# KeyboardMoudle2.net
KiCad netlist of a schematic drawn in Altium Designer
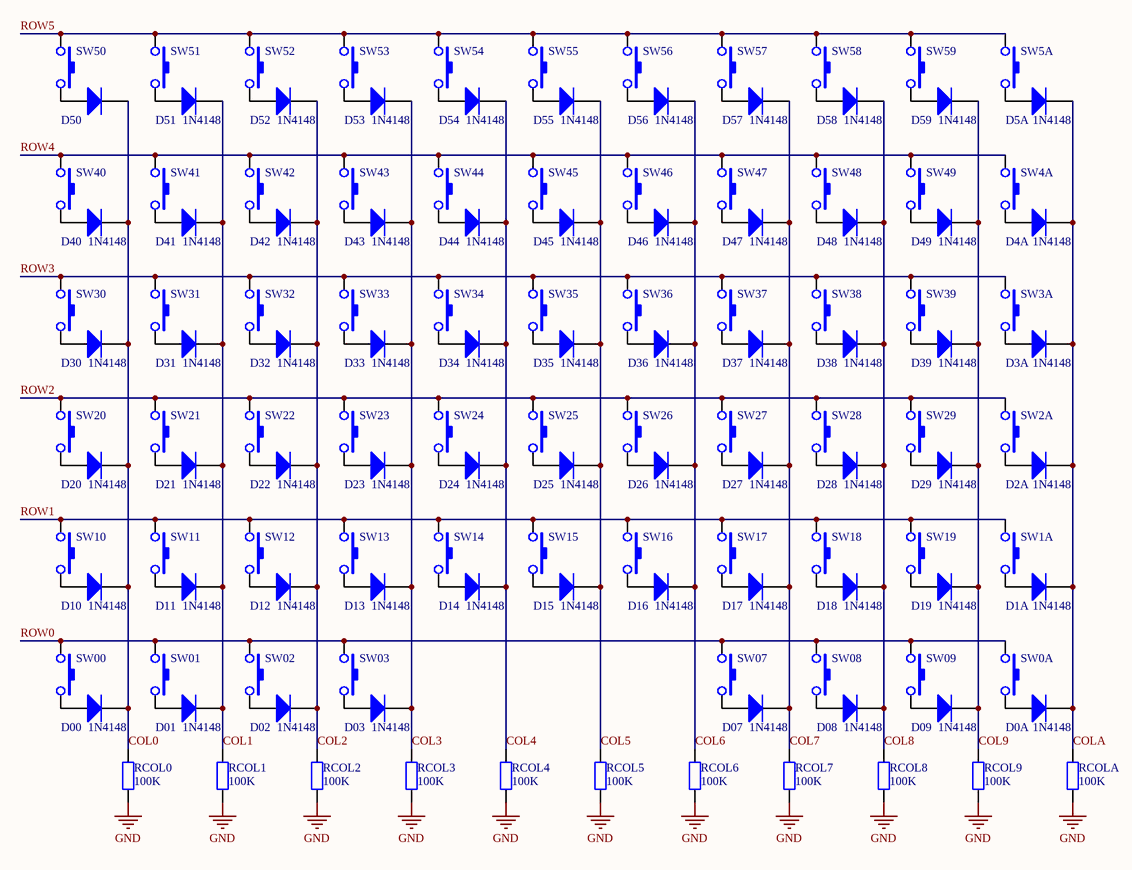
[diagram p0: KeyboardMoudle2.SchDoc]

(export (version "E")
  (design (tool "Eeschema 10.0.6"))
  (components
    (comp (ref "D00")
      (value "1N4148")
      (footprint "SOD523")
      (description "开关二极管")
      (libsource (lib "MT_Device") (part "DIO_1N4148_SOD523"))
    )
    (comp (ref "D0A")
      (value "1N4148")
      (footprint "SOD523")
      (description "开关二极管")
      (libsource (lib "MT_Device") (part "DIO_1N4148_SOD523"))
    )
    (comp (ref "D01")
      (value "1N4148")
      (footprint "SOD523")
      (description "开关二极管")
      (libsource (lib "MT_Device") (part "DIO_1N4148_SOD523"))
    )
    (comp (ref "D1A")
      (value "1N4148")
      (footprint "SOD523")
      (description "开关二极管")
      (libsource (lib "MT_Device") (part "DIO_1N4148_SOD523"))
    )
    (comp (ref "D02")
      (value "1N4148")
      (footprint "SOD523")
      (description "开关二极管")
      (libsource (lib "MT_Device") (part "DIO_1N4148_SOD523"))
    )
    (comp (ref "D2A")
      (value "1N4148")
      (footprint "SOD523")
      (description "开关二极管")
      (libsource (lib "MT_Device") (part "DIO_1N4148_SOD523"))
    )
    (comp (ref "D03")
      (value "1N4148")
      (footprint "SOD523")
      (description "开关二极管")
      (libsource (lib "MT_Device") (part "DIO_1N4148_SOD523"))
    )
    (comp (ref "D3A")
      (value "1N4148")
      (footprint "SOD523")
      (description "开关二极管")
      (libsource (lib "MT_Device") (part "DIO_1N4148_SOD523"))
    )
    (comp (ref "D4A")
      (value "1N4148")
      (footprint "SOD523")
      (description "开关二极管")
      (libsource (lib "MT_Device") (part "DIO_1N4148_SOD523"))
    )
    (comp (ref "D5A")
      (value "1N4148")
      (footprint "SOD523")
      (description "开关二极管")
      (libsource (lib "MT_Device") (part "DIO_1N4148_SOD523"))
    )
    (comp (ref "D07")
      (value "1N4148")
      (footprint "SOD523")
      (description "开关二极管")
      (libsource (lib "MT_Device") (part "DIO_1N4148_SOD523"))
    )
    (comp (ref "D08")
      (value "1N4148")
      (footprint "SOD523")
      (description "开关二极管")
      (libsource (lib "MT_Device") (part "DIO_1N4148_SOD523"))
    )
    (comp (ref "D09")
      (value "1N4148")
      (footprint "SOD523")
      (description "开关二极管")
      (libsource (lib "MT_Device") (part "DIO_1N4148_SOD523"))
    )
    (comp (ref "D10")
      (value "1N4148")
      (footprint "SOD523")
      (description "开关二极管")
      (libsource (lib "MT_Device") (part "DIO_1N4148_SOD523"))
    )
    (comp (ref "D11")
      (value "1N4148")
      (footprint "SOD523")
      (description "开关二极管")
      (libsource (lib "MT_Device") (part "DIO_1N4148_SOD523"))
    )
    (comp (ref "D12")
      (value "1N4148")
      (footprint "SOD523")
      (description "开关二极管")
      (libsource (lib "MT_Device") (part "DIO_1N4148_SOD523"))
    )
    (comp (ref "D13")
      (value "1N4148")
      (footprint "SOD523")
      (description "开关二极管")
      (libsource (lib "MT_Device") (part "DIO_1N4148_SOD523"))
    )
    (comp (ref "D14")
      (value "1N4148")
      (footprint "SOD523")
      (description "开关二极管")
      (libsource (lib "MT_Device") (part "DIO_1N4148_SOD523"))
    )
    (comp (ref "D15")
      (value "1N4148")
      (footprint "SOD523")
      (description "开关二极管")
      (libsource (lib "MT_Device") (part "DIO_1N4148_SOD523"))
    )
    (comp (ref "D16")
      (value "1N4148")
      (footprint "SOD523")
      (description "开关二极管")
      (libsource (lib "MT_Device") (part "DIO_1N4148_SOD523"))
    )
    (comp (ref "D17")
      (value "1N4148")
      (footprint "SOD523")
      (description "开关二极管")
      (libsource (lib "MT_Device") (part "DIO_1N4148_SOD523"))
    )
    (comp (ref "D18")
      (value "1N4148")
      (footprint "SOD523")
      (description "开关二极管")
      (libsource (lib "MT_Device") (part "DIO_1N4148_SOD523"))
    )
    (comp (ref "D19")
      (value "1N4148")
      (footprint "SOD523")
      (description "开关二极管")
      (libsource (lib "MT_Device") (part "DIO_1N4148_SOD523"))
    )
    (comp (ref "D20")
      (value "1N4148")
      (footprint "SOD523")
      (description "开关二极管")
      (libsource (lib "MT_Device") (part "DIO_1N4148_SOD523"))
    )
    (comp (ref "D21")
      (value "1N4148")
      (footprint "SOD523")
      (description "开关二极管")
      (libsource (lib "MT_Device") (part "DIO_1N4148_SOD523"))
    )
    (comp (ref "D22")
      (value "1N4148")
      (footprint "SOD523")
      (description "开关二极管")
      (libsource (lib "MT_Device") (part "DIO_1N4148_SOD523"))
    )
    (comp (ref "D23")
      (value "1N4148")
      (footprint "SOD523")
      (description "开关二极管")
      (libsource (lib "MT_Device") (part "DIO_1N4148_SOD523"))
    )
    (comp (ref "D24")
      (value "1N4148")
      (footprint "SOD523")
      (description "开关二极管")
      (libsource (lib "MT_Device") (part "DIO_1N4148_SOD523"))
    )
    (comp (ref "D25")
      (value "1N4148")
      (footprint "SOD523")
      (description "开关二极管")
      (libsource (lib "MT_Device") (part "DIO_1N4148_SOD523"))
    )
    (comp (ref "D26")
      (value "1N4148")
      (footprint "SOD523")
      (description "开关二极管")
      (libsource (lib "MT_Device") (part "DIO_1N4148_SOD523"))
    )
    (comp (ref "D27")
      (value "1N4148")
      (footprint "SOD523")
      (description "开关二极管")
      (libsource (lib "MT_Device") (part "DIO_1N4148_SOD523"))
    )
    (comp (ref "D28")
      (value "1N4148")
      (footprint "SOD523")
      (description "开关二极管")
      (libsource (lib "MT_Device") (part "DIO_1N4148_SOD523"))
    )
    (comp (ref "D29")
      (value "1N4148")
      (footprint "SOD523")
      (description "开关二极管")
      (libsource (lib "MT_Device") (part "DIO_1N4148_SOD523"))
    )
    (comp (ref "D30")
      (value "1N4148")
      (footprint "SOD523")
      (description "开关二极管")
      (libsource (lib "MT_Device") (part "DIO_1N4148_SOD523"))
    )
    (comp (ref "D31")
      (value "1N4148")
      (footprint "SOD523")
      (description "开关二极管")
      (libsource (lib "MT_Device") (part "DIO_1N4148_SOD523"))
    )
    (comp (ref "D32")
      (value "1N4148")
      (footprint "SOD523")
      (description "开关二极管")
      (libsource (lib "MT_Device") (part "DIO_1N4148_SOD523"))
    )
    (comp (ref "D33")
      (value "1N4148")
      (footprint "SOD523")
      (description "开关二极管")
      (libsource (lib "MT_Device") (part "DIO_1N4148_SOD523"))
    )
    (comp (ref "D34")
      (value "1N4148")
      (footprint "SOD523")
      (description "开关二极管")
      (libsource (lib "MT_Device") (part "DIO_1N4148_SOD523"))
    )
    (comp (ref "D35")
      (value "1N4148")
      (footprint "SOD523")
      (description "开关二极管")
      (libsource (lib "MT_Device") (part "DIO_1N4148_SOD523"))
    )
    (comp (ref "D36")
      (value "1N4148")
      (footprint "SOD523")
      (description "开关二极管")
      (libsource (lib "MT_Device") (part "DIO_1N4148_SOD523"))
    )
    (comp (ref "D37")
      (value "1N4148")
      (footprint "SOD523")
      (description "开关二极管")
      (libsource (lib "MT_Device") (part "DIO_1N4148_SOD523"))
    )
    (comp (ref "D38")
      (value "1N4148")
      (footprint "SOD523")
      (description "开关二极管")
      (libsource (lib "MT_Device") (part "DIO_1N4148_SOD523"))
    )
    (comp (ref "D39")
      (value "1N4148")
      (footprint "SOD523")
      (description "开关二极管")
      (libsource (lib "MT_Device") (part "DIO_1N4148_SOD523"))
    )
    (comp (ref "D40")
      (value "1N4148")
      (footprint "SOD523")
      (description "开关二极管")
      (libsource (lib "MT_Device") (part "DIO_1N4148_SOD523"))
    )
    (comp (ref "D41")
      (value "1N4148")
      (footprint "SOD523")
      (description "开关二极管")
      (libsource (lib "MT_Device") (part "DIO_1N4148_SOD523"))
    )
    (comp (ref "D42")
      (value "1N4148")
      (footprint "SOD523")
      (description "开关二极管")
      (libsource (lib "MT_Device") (part "DIO_1N4148_SOD523"))
    )
    (comp (ref "D43")
      (value "1N4148")
      (footprint "SOD523")
      (description "开关二极管")
      (libsource (lib "MT_Device") (part "DIO_1N4148_SOD523"))
    )
    (comp (ref "D44")
      (value "1N4148")
      (footprint "SOD523")
      (description "开关二极管")
      (libsource (lib "MT_Device") (part "DIO_1N4148_SOD523"))
    )
    (comp (ref "D45")
      (value "1N4148")
      (footprint "SOD523")
      (description "开关二极管")
      (libsource (lib "MT_Device") (part "DIO_1N4148_SOD523"))
    )
    (comp (ref "D46")
      (value "1N4148")
      (footprint "SOD523")
      (description "开关二极管")
      (libsource (lib "MT_Device") (part "DIO_1N4148_SOD523"))
    )
    (comp (ref "D47")
      (value "1N4148")
      (footprint "SOD523")
      (description "开关二极管")
      (libsource (lib "MT_Device") (part "DIO_1N4148_SOD523"))
    )
    (comp (ref "D48")
      (value "1N4148")
      (footprint "SOD523")
      (description "开关二极管")
      (libsource (lib "MT_Device") (part "DIO_1N4148_SOD523"))
    )
    (comp (ref "D49")
      (value "1N4148")
      (footprint "SOD523")
      (description "开关二极管")
      (libsource (lib "MT_Device") (part "DIO_1N4148_SOD523"))
    )
    (comp (ref "D50")
      (value "~")
      (footprint "SOD523")
      (description "开关二极管")
      (libsource (lib "MT_Device") (part "DIO_1N4148_SOD523"))
    )
    (comp (ref "D51")
      (value "1N4148")
      (footprint "SOD523")
      (description "开关二极管")
      (libsource (lib "MT_Device") (part "DIO_1N4148_SOD523"))
    )
    (comp (ref "D52")
      (value "1N4148")
      (footprint "SOD523")
      (description "开关二极管")
      (libsource (lib "MT_Device") (part "DIO_1N4148_SOD523"))
    )
    (comp (ref "D53")
      (value "1N4148")
      (footprint "SOD523")
      (description "开关二极管")
      (libsource (lib "MT_Device") (part "DIO_1N4148_SOD523"))
    )
    (comp (ref "D54")
      (value "1N4148")
      (footprint "SOD523")
      (description "开关二极管")
      (libsource (lib "MT_Device") (part "DIO_1N4148_SOD523"))
    )
    (comp (ref "D55")
      (value "1N4148")
      (footprint "SOD523")
      (description "开关二极管")
      (libsource (lib "MT_Device") (part "DIO_1N4148_SOD523"))
    )
    (comp (ref "D56")
      (value "1N4148")
      (footprint "SOD523")
      (description "开关二极管")
      (libsource (lib "MT_Device") (part "DIO_1N4148_SOD523"))
    )
    (comp (ref "D57")
      (value "1N4148")
      (footprint "SOD523")
      (description "开关二极管")
      (libsource (lib "MT_Device") (part "DIO_1N4148_SOD523"))
    )
    (comp (ref "D58")
      (value "1N4148")
      (footprint "SOD523")
      (description "开关二极管")
      (libsource (lib "MT_Device") (part "DIO_1N4148_SOD523"))
    )
    (comp (ref "D59")
      (value "1N4148")
      (footprint "SOD523")
      (description "开关二极管")
      (libsource (lib "MT_Device") (part "DIO_1N4148_SOD523"))
    )
    (comp (ref "RCOL0")
      (value "100K")
      (footprint "R_0603")
      (description "电阻 0603")
      (libsource (lib "MT_Device") (part "RES_0603"))
    )
    (comp (ref "RCOL1")
      (value "100K")
      (footprint "R_0603")
      (description "电阻 0603")
      (libsource (lib "MT_Device") (part "RES_0603"))
    )
    (comp (ref "RCOL2")
      (value "100K")
      (footprint "R_0603")
      (description "电阻 0603")
      (libsource (lib "MT_Device") (part "RES_0603"))
    )
    (comp (ref "RCOL3")
      (value "100K")
      (footprint "R_0603")
      (description "电阻 0603")
      (libsource (lib "MT_Device") (part "RES_0603"))
    )
    (comp (ref "RCOL4")
      (value "100K")
      (footprint "R_0603")
      (description "电阻 0603")
      (libsource (lib "MT_Device") (part "RES_0603"))
    )
    (comp (ref "RCOL5")
      (value "100K")
      (footprint "R_0603")
      (description "电阻 0603")
      (libsource (lib "MT_Device") (part "RES_0603"))
    )
    (comp (ref "RCOL6")
      (value "100K")
      (footprint "R_0603")
      (description "电阻 0603")
      (libsource (lib "MT_Device") (part "RES_0603"))
    )
    (comp (ref "RCOL7")
      (value "100K")
      (footprint "R_0603")
      (description "电阻 0603")
      (libsource (lib "MT_Device") (part "RES_0603"))
    )
    (comp (ref "RCOL8")
      (value "100K")
      (footprint "R_0603")
      (description "电阻 0603")
      (libsource (lib "MT_Device") (part "RES_0603"))
    )
    (comp (ref "RCOL9")
      (value "100K")
      (footprint "R_0603")
      (description "电阻 0603")
      (libsource (lib "MT_Device") (part "RES_0603"))
    )
    (comp (ref "RCOLA")
      (value "100K")
      (footprint "R_0603")
      (description "电阻 0603")
      (libsource (lib "MT_Device") (part "RES_0603"))
    )
    (comp (ref "SW00")
      (value "SWITCH_KAILH_1350")
      (footprint "SWITCH_KAILH_1350")
      (description "凯华机械矮轴1350")
      (libsource (lib "MT_Device") (part "SWITCH_KAILH_1350"))
    )
    (comp (ref "SW0A")
      (value "SWITCH_KAILH_1350")
      (footprint "SWITCH_KAILH_1350")
      (description "凯华机械矮轴1350")
      (libsource (lib "MT_Device") (part "SWITCH_KAILH_1350"))
    )
    (comp (ref "SW01")
      (value "SWITCH_KAILH_1350")
      (footprint "SWITCH_KAILH_1350")
      (description "凯华机械矮轴1350")
      (libsource (lib "MT_Device") (part "SWITCH_KAILH_1350"))
    )
    (comp (ref "SW1A")
      (value "SWITCH_KAILH_1350")
      (footprint "SWITCH_KAILH_1350")
      (description "凯华机械矮轴1350")
      (libsource (lib "MT_Device") (part "SWITCH_KAILH_1350"))
    )
    (comp (ref "SW02")
      (value "SWITCH_KAILH_1350")
      (footprint "SWITCH_KAILH_1350")
      (description "凯华机械矮轴1350")
      (libsource (lib "MT_Device") (part "SWITCH_KAILH_1350"))
    )
    (comp (ref "SW2A")
      (value "SWITCH_KAILH_1350")
      (footprint "SWITCH_KAILH_1350")
      (description "凯华机械矮轴1350")
      (libsource (lib "MT_Device") (part "SWITCH_KAILH_1350"))
    )
    (comp (ref "SW03")
      (value "SWITCH_KAILH_1350")
      (footprint "SWITCH_KAILH_1350")
      (description "凯华机械矮轴1350")
      (libsource (lib "MT_Device") (part "SWITCH_KAILH_1350"))
    )
    (comp (ref "SW3A")
      (value "SWITCH_KAILH_1350")
      (footprint "SWITCH_KAILH_1350")
      (description "凯华机械矮轴1350")
      (libsource (lib "MT_Device") (part "SWITCH_KAILH_1350"))
    )
    (comp (ref "SW4A")
      (value "SWITCH_KAILH_1350")
      (footprint "SWITCH_KAILH_1350")
      (description "凯华机械矮轴1350")
      (libsource (lib "MT_Device") (part "SWITCH_KAILH_1350"))
    )
    (comp (ref "SW5A")
      (value "SWITCH_KAILH_1350")
      (footprint "SWITCH_KAILH_1350")
      (description "凯华机械矮轴1350")
      (libsource (lib "MT_Device") (part "SWITCH_KAILH_1350"))
    )
    (comp (ref "SW07")
      (value "SWITCH_KAILH_1350")
      (footprint "SWITCH_KAILH_1350")
      (description "凯华机械矮轴1350")
      (libsource (lib "MT_Device") (part "SWITCH_KAILH_1350"))
    )
    (comp (ref "SW08")
      (value "SWITCH_KAILH_1350")
      (footprint "SWITCH_KAILH_1350")
      (description "凯华机械矮轴1350")
      (libsource (lib "MT_Device") (part "SWITCH_KAILH_1350"))
    )
    (comp (ref "SW09")
      (value "SWITCH_KAILH_1350")
      (footprint "SWITCH_KAILH_1350")
      (description "凯华机械矮轴1350")
      (libsource (lib "MT_Device") (part "SWITCH_KAILH_1350"))
    )
    (comp (ref "SW10")
      (value "SWITCH_KAILH_1350")
      (footprint "SWITCH_KAILH_1350")
      (description "凯华机械矮轴1350")
      (libsource (lib "MT_Device") (part "SWITCH_KAILH_1350"))
    )
    (comp (ref "SW11")
      (value "SWITCH_KAILH_1350")
      (footprint "SWITCH_KAILH_1350")
      (description "凯华机械矮轴1350")
      (libsource (lib "MT_Device") (part "SWITCH_KAILH_1350"))
    )
    (comp (ref "SW12")
      (value "SWITCH_KAILH_1350")
      (footprint "SWITCH_KAILH_1350")
      (description "凯华机械矮轴1350")
      (libsource (lib "MT_Device") (part "SWITCH_KAILH_1350"))
    )
    (comp (ref "SW13")
      (value "SWITCH_KAILH_1350")
      (footprint "SWITCH_KAILH_1350")
      (description "凯华机械矮轴1350")
      (libsource (lib "MT_Device") (part "SWITCH_KAILH_1350"))
    )
    (comp (ref "SW14")
      (value "SWITCH_KAILH_1350")
      (footprint "SWITCH_KAILH_1350")
      (description "凯华机械矮轴1350")
      (libsource (lib "MT_Device") (part "SWITCH_KAILH_1350"))
    )
    (comp (ref "SW15")
      (value "SWITCH_KAILH_1350")
      (footprint "SWITCH_KAILH_1350")
      (description "凯华机械矮轴1350")
      (libsource (lib "MT_Device") (part "SWITCH_KAILH_1350"))
    )
    (comp (ref "SW16")
      (value "SWITCH_KAILH_1350")
      (footprint "SWITCH_KAILH_1350")
      (description "凯华机械矮轴1350")
      (libsource (lib "MT_Device") (part "SWITCH_KAILH_1350"))
    )
    (comp (ref "SW17")
      (value "SWITCH_KAILH_1350")
      (footprint "SWITCH_KAILH_1350")
      (description "凯华机械矮轴1350")
      (libsource (lib "MT_Device") (part "SWITCH_KAILH_1350"))
    )
    (comp (ref "SW18")
      (value "SWITCH_KAILH_1350")
      (footprint "SWITCH_KAILH_1350")
      (description "凯华机械矮轴1350")
      (libsource (lib "MT_Device") (part "SWITCH_KAILH_1350"))
    )
    (comp (ref "SW19")
      (value "SWITCH_KAILH_1350")
      (footprint "SWITCH_KAILH_1350")
      (description "凯华机械矮轴1350")
      (libsource (lib "MT_Device") (part "SWITCH_KAILH_1350"))
    )
    (comp (ref "SW20")
      (value "SWITCH_KAILH_1350")
      (footprint "SWITCH_KAILH_1350")
      (description "凯华机械矮轴1350")
      (libsource (lib "MT_Device") (part "SWITCH_KAILH_1350"))
    )
    (comp (ref "SW21")
      (value "SWITCH_KAILH_1350")
      (footprint "SWITCH_KAILH_1350")
      (description "凯华机械矮轴1350")
      (libsource (lib "MT_Device") (part "SWITCH_KAILH_1350"))
    )
    (comp (ref "SW22")
      (value "SWITCH_KAILH_1350")
      (footprint "SWITCH_KAILH_1350")
      (description "凯华机械矮轴1350")
      (libsource (lib "MT_Device") (part "SWITCH_KAILH_1350"))
    )
    (comp (ref "SW23")
      (value "SWITCH_KAILH_1350")
      (footprint "SWITCH_KAILH_1350")
      (description "凯华机械矮轴1350")
      (libsource (lib "MT_Device") (part "SWITCH_KAILH_1350"))
    )
    (comp (ref "SW24")
      (value "SWITCH_KAILH_1350")
      (footprint "SWITCH_KAILH_1350")
      (description "凯华机械矮轴1350")
      (libsource (lib "MT_Device") (part "SWITCH_KAILH_1350"))
    )
    (comp (ref "SW25")
      (value "SWITCH_KAILH_1350")
      (footprint "SWITCH_KAILH_1350")
      (description "凯华机械矮轴1350")
      (libsource (lib "MT_Device") (part "SWITCH_KAILH_1350"))
    )
    (comp (ref "SW26")
      (value "SWITCH_KAILH_1350")
      (footprint "SWITCH_KAILH_1350")
      (description "凯华机械矮轴1350")
      (libsource (lib "MT_Device") (part "SWITCH_KAILH_1350"))
    )
    (comp (ref "SW27")
      (value "SWITCH_KAILH_1350")
      (footprint "SWITCH_KAILH_1350")
      (description "凯华机械矮轴1350")
      (libsource (lib "MT_Device") (part "SWITCH_KAILH_1350"))
    )
    (comp (ref "SW28")
      (value "SWITCH_KAILH_1350")
      (footprint "SWITCH_KAILH_1350")
      (description "凯华机械矮轴1350")
      (libsource (lib "MT_Device") (part "SWITCH_KAILH_1350"))
    )
    (comp (ref "SW29")
      (value "SWITCH_KAILH_1350")
      (footprint "SWITCH_KAILH_1350")
      (description "凯华机械矮轴1350")
      (libsource (lib "MT_Device") (part "SWITCH_KAILH_1350"))
    )
    (comp (ref "SW30")
      (value "SWITCH_KAILH_1350")
      (footprint "SWITCH_KAILH_1350")
      (description "凯华机械矮轴1350")
      (libsource (lib "MT_Device") (part "SWITCH_KAILH_1350"))
    )
    (comp (ref "SW31")
      (value "SWITCH_KAILH_1350")
      (footprint "SWITCH_KAILH_1350")
      (description "凯华机械矮轴1350")
      (libsource (lib "MT_Device") (part "SWITCH_KAILH_1350"))
    )
    (comp (ref "SW32")
      (value "SWITCH_KAILH_1350")
      (footprint "SWITCH_KAILH_1350")
      (description "凯华机械矮轴1350")
      (libsource (lib "MT_Device") (part "SWITCH_KAILH_1350"))
    )
    (comp (ref "SW33")
      (value "SWITCH_KAILH_1350")
      (footprint "SWITCH_KAILH_1350")
      (description "凯华机械矮轴1350")
      (libsource (lib "MT_Device") (part "SWITCH_KAILH_1350"))
    )
    (comp (ref "SW34")
      (value "SWITCH_KAILH_1350")
      (footprint "SWITCH_KAILH_1350")
      (description "凯华机械矮轴1350")
      (libsource (lib "MT_Device") (part "SWITCH_KAILH_1350"))
    )
    (comp (ref "SW35")
      (value "SWITCH_KAILH_1350")
      (footprint "SWITCH_KAILH_1350")
      (description "凯华机械矮轴1350")
      (libsource (lib "MT_Device") (part "SWITCH_KAILH_1350"))
    )
    (comp (ref "SW36")
      (value "SWITCH_KAILH_1350")
      (footprint "SWITCH_KAILH_1350")
      (description "凯华机械矮轴1350")
      (libsource (lib "MT_Device") (part "SWITCH_KAILH_1350"))
    )
    (comp (ref "SW37")
      (value "SWITCH_KAILH_1350")
      (footprint "SWITCH_KAILH_1350")
      (description "凯华机械矮轴1350")
      (libsource (lib "MT_Device") (part "SWITCH_KAILH_1350"))
    )
    (comp (ref "SW38")
      (value "SWITCH_KAILH_1350")
      (footprint "SWITCH_KAILH_1350")
      (description "凯华机械矮轴1350")
      (libsource (lib "MT_Device") (part "SWITCH_KAILH_1350"))
    )
    (comp (ref "SW39")
      (value "SWITCH_KAILH_1350")
      (footprint "SWITCH_KAILH_1350")
      (description "凯华机械矮轴1350")
      (libsource (lib "MT_Device") (part "SWITCH_KAILH_1350"))
    )
    (comp (ref "SW40")
      (value "SWITCH_KAILH_1350")
      (footprint "SWITCH_KAILH_1350")
      (description "凯华机械矮轴1350")
      (libsource (lib "MT_Device") (part "SWITCH_KAILH_1350"))
    )
    (comp (ref "SW41")
      (value "SWITCH_KAILH_1350")
      (footprint "SWITCH_KAILH_1350")
      (description "凯华机械矮轴1350")
      (libsource (lib "MT_Device") (part "SWITCH_KAILH_1350"))
    )
    (comp (ref "SW42")
      (value "SWITCH_KAILH_1350")
      (footprint "SWITCH_KAILH_1350")
      (description "凯华机械矮轴1350")
      (libsource (lib "MT_Device") (part "SWITCH_KAILH_1350"))
    )
    (comp (ref "SW43")
      (value "SWITCH_KAILH_1350")
      (footprint "SWITCH_KAILH_1350")
      (description "凯华机械矮轴1350")
      (libsource (lib "MT_Device") (part "SWITCH_KAILH_1350"))
    )
    (comp (ref "SW44")
      (value "SWITCH_KAILH_1350")
      (footprint "SWITCH_KAILH_1350")
      (description "凯华机械矮轴1350")
      (libsource (lib "MT_Device") (part "SWITCH_KAILH_1350"))
    )
    (comp (ref "SW45")
      (value "SWITCH_KAILH_1350")
      (footprint "SWITCH_KAILH_1350")
      (description "凯华机械矮轴1350")
      (libsource (lib "MT_Device") (part "SWITCH_KAILH_1350"))
    )
    (comp (ref "SW46")
      (value "SWITCH_KAILH_1350")
      (footprint "SWITCH_KAILH_1350")
      (description "凯华机械矮轴1350")
      (libsource (lib "MT_Device") (part "SWITCH_KAILH_1350"))
    )
    (comp (ref "SW47")
      (value "SWITCH_KAILH_1350")
      (footprint "SWITCH_KAILH_1350")
      (description "凯华机械矮轴1350")
      (libsource (lib "MT_Device") (part "SWITCH_KAILH_1350"))
    )
    (comp (ref "SW48")
      (value "SWITCH_KAILH_1350")
      (footprint "SWITCH_KAILH_1350")
      (description "凯华机械矮轴1350")
      (libsource (lib "MT_Device") (part "SWITCH_KAILH_1350"))
    )
    (comp (ref "SW49")
      (value "SWITCH_KAILH_1350")
      (footprint "SWITCH_KAILH_1350")
      (description "凯华机械矮轴1350")
      (libsource (lib "MT_Device") (part "SWITCH_KAILH_1350"))
    )
    (comp (ref "SW50")
      (value "SWITCH_KAILH_1350")
      (footprint "SWITCH_KAILH_1350")
      (description "凯华机械矮轴1350")
      (libsource (lib "MT_Device") (part "SWITCH_KAILH_1350"))
    )
    (comp (ref "SW51")
      (value "SWITCH_KAILH_1350")
      (footprint "SWITCH_KAILH_1350")
      (description "凯华机械矮轴1350")
      (libsource (lib "MT_Device") (part "SWITCH_KAILH_1350"))
    )
    (comp (ref "SW52")
      (value "SWITCH_KAILH_1350")
      (footprint "SWITCH_KAILH_1350")
      (description "凯华机械矮轴1350")
      (libsource (lib "MT_Device") (part "SWITCH_KAILH_1350"))
    )
    (comp (ref "SW53")
      (value "SWITCH_KAILH_1350")
      (footprint "SWITCH_KAILH_1350")
      (description "凯华机械矮轴1350")
      (libsource (lib "MT_Device") (part "SWITCH_KAILH_1350"))
    )
    (comp (ref "SW54")
      (value "SWITCH_KAILH_1350")
      (footprint "SWITCH_KAILH_1350")
      (description "凯华机械矮轴1350")
      (libsource (lib "MT_Device") (part "SWITCH_KAILH_1350"))
    )
    (comp (ref "SW55")
      (value "SWITCH_KAILH_1350")
      (footprint "SWITCH_KAILH_1350")
      (description "凯华机械矮轴1350")
      (libsource (lib "MT_Device") (part "SWITCH_KAILH_1350"))
    )
    (comp (ref "SW56")
      (value "SWITCH_KAILH_1350")
      (footprint "SWITCH_KAILH_1350")
      (description "凯华机械矮轴1350")
      (libsource (lib "MT_Device") (part "SWITCH_KAILH_1350"))
    )
    (comp (ref "SW57")
      (value "SWITCH_KAILH_1350")
      (footprint "SWITCH_KAILH_1350")
      (description "凯华机械矮轴1350")
      (libsource (lib "MT_Device") (part "SWITCH_KAILH_1350"))
    )
    (comp (ref "SW58")
      (value "SWITCH_KAILH_1350")
      (footprint "SWITCH_KAILH_1350")
      (description "凯华机械矮轴1350")
      (libsource (lib "MT_Device") (part "SWITCH_KAILH_1350"))
    )
    (comp (ref "SW59")
      (value "SWITCH_KAILH_1350")
      (footprint "SWITCH_KAILH_1350")
      (description "凯华机械矮轴1350")
      (libsource (lib "MT_Device") (part "SWITCH_KAILH_1350"))
    )
  )
  (nets
    (net (code "1") (name "/COL0") (class "Default")
      (node (ref "D00") (pin "2") (pinfunction "K_2") (pintype "passive"))
      (node (ref "D10") (pin "2") (pinfunction "K_2") (pintype "passive"))
      (node (ref "D20") (pin "2") (pinfunction "K_2") (pintype "passive"))
      (node (ref "D30") (pin "2") (pinfunction "K_2") (pintype "passive"))
      (node (ref "D40") (pin "2") (pinfunction "K_2") (pintype "passive"))
      (node (ref "D50") (pin "2") (pinfunction "K_2") (pintype "passive"))
      (node (ref "RCOL0") (pin "2") (pinfunction "2_2") (pintype "passive"))
    )
    (net (code "2") (name "/COL1") (class "Default")
      (node (ref "D01") (pin "2") (pinfunction "K_2") (pintype "passive"))
      (node (ref "D11") (pin "2") (pinfunction "K_2") (pintype "passive"))
      (node (ref "D21") (pin "2") (pinfunction "K_2") (pintype "passive"))
      (node (ref "D31") (pin "2") (pinfunction "K_2") (pintype "passive"))
      (node (ref "D41") (pin "2") (pinfunction "K_2") (pintype "passive"))
      (node (ref "D51") (pin "2") (pinfunction "K_2") (pintype "passive"))
      (node (ref "RCOL1") (pin "2") (pinfunction "2_2") (pintype "passive"))
    )
    (net (code "3") (name "/COL2") (class "Default")
      (node (ref "D02") (pin "2") (pinfunction "K_2") (pintype "passive"))
      (node (ref "D12") (pin "2") (pinfunction "K_2") (pintype "passive"))
      (node (ref "D22") (pin "2") (pinfunction "K_2") (pintype "passive"))
      (node (ref "D32") (pin "2") (pinfunction "K_2") (pintype "passive"))
      (node (ref "D42") (pin "2") (pinfunction "K_2") (pintype "passive"))
      (node (ref "D52") (pin "2") (pinfunction "K_2") (pintype "passive"))
      (node (ref "RCOL2") (pin "2") (pinfunction "2_2") (pintype "passive"))
    )
    (net (code "4") (name "/COL3") (class "Default")
      (node (ref "D03") (pin "2") (pinfunction "K_2") (pintype "passive"))
      (node (ref "D13") (pin "2") (pinfunction "K_2") (pintype "passive"))
      (node (ref "D23") (pin "2") (pinfunction "K_2") (pintype "passive"))
      (node (ref "D33") (pin "2") (pinfunction "K_2") (pintype "passive"))
      (node (ref "D43") (pin "2") (pinfunction "K_2") (pintype "passive"))
      (node (ref "D53") (pin "2") (pinfunction "K_2") (pintype "passive"))
      (node (ref "RCOL3") (pin "2") (pinfunction "2_2") (pintype "passive"))
    )
    (net (code "5") (name "/COL4") (class "Default")
      (node (ref "D14") (pin "2") (pinfunction "K_2") (pintype "passive"))
      (node (ref "D24") (pin "2") (pinfunction "K_2") (pintype "passive"))
      (node (ref "D34") (pin "2") (pinfunction "K_2") (pintype "passive"))
      (node (ref "D44") (pin "2") (pinfunction "K_2") (pintype "passive"))
      (node (ref "D54") (pin "2") (pinfunction "K_2") (pintype "passive"))
      (node (ref "RCOL4") (pin "2") (pinfunction "2_2") (pintype "passive"))
    )
    (net (code "6") (name "/COL5") (class "Default")
      (node (ref "D15") (pin "2") (pinfunction "K_2") (pintype "passive"))
      (node (ref "D25") (pin "2") (pinfunction "K_2") (pintype "passive"))
      (node (ref "D35") (pin "2") (pinfunction "K_2") (pintype "passive"))
      (node (ref "D45") (pin "2") (pinfunction "K_2") (pintype "passive"))
      (node (ref "D55") (pin "2") (pinfunction "K_2") (pintype "passive"))
      (node (ref "RCOL5") (pin "2") (pinfunction "2_2") (pintype "passive"))
    )
    (net (code "7") (name "/COL6") (class "Default")
      (node (ref "D16") (pin "2") (pinfunction "K_2") (pintype "passive"))
      (node (ref "D26") (pin "2") (pinfunction "K_2") (pintype "passive"))
      (node (ref "D36") (pin "2") (pinfunction "K_2") (pintype "passive"))
      (node (ref "D46") (pin "2") (pinfunction "K_2") (pintype "passive"))
      (node (ref "D56") (pin "2") (pinfunction "K_2") (pintype "passive"))
      (node (ref "RCOL6") (pin "2") (pinfunction "2_2") (pintype "passive"))
    )
    (net (code "8") (name "/COL7") (class "Default")
      (node (ref "D07") (pin "2") (pinfunction "K_2") (pintype "passive"))
      (node (ref "D17") (pin "2") (pinfunction "K_2") (pintype "passive"))
      (node (ref "D27") (pin "2") (pinfunction "K_2") (pintype "passive"))
      (node (ref "D37") (pin "2") (pinfunction "K_2") (pintype "passive"))
      (node (ref "D47") (pin "2") (pinfunction "K_2") (pintype "passive"))
      (node (ref "D57") (pin "2") (pinfunction "K_2") (pintype "passive"))
      (node (ref "RCOL7") (pin "2") (pinfunction "2_2") (pintype "passive"))
    )
    (net (code "9") (name "/COL8") (class "Default")
      (node (ref "D08") (pin "2") (pinfunction "K_2") (pintype "passive"))
      (node (ref "D18") (pin "2") (pinfunction "K_2") (pintype "passive"))
      (node (ref "D28") (pin "2") (pinfunction "K_2") (pintype "passive"))
      (node (ref "D38") (pin "2") (pinfunction "K_2") (pintype "passive"))
      (node (ref "D48") (pin "2") (pinfunction "K_2") (pintype "passive"))
      (node (ref "D58") (pin "2") (pinfunction "K_2") (pintype "passive"))
      (node (ref "RCOL8") (pin "2") (pinfunction "2_2") (pintype "passive"))
    )
    (net (code "10") (name "/COL9") (class "Default")
      (node (ref "D09") (pin "2") (pinfunction "K_2") (pintype "passive"))
      (node (ref "D19") (pin "2") (pinfunction "K_2") (pintype "passive"))
      (node (ref "D29") (pin "2") (pinfunction "K_2") (pintype "passive"))
      (node (ref "D39") (pin "2") (pinfunction "K_2") (pintype "passive"))
      (node (ref "D49") (pin "2") (pinfunction "K_2") (pintype "passive"))
      (node (ref "D59") (pin "2") (pinfunction "K_2") (pintype "passive"))
      (node (ref "RCOL9") (pin "2") (pinfunction "2_2") (pintype "passive"))
    )
    (net (code "11") (name "/COLA") (class "Default")
      (node (ref "D0A") (pin "2") (pinfunction "K_2") (pintype "passive"))
      (node (ref "D1A") (pin "2") (pinfunction "K_2") (pintype "passive"))
      (node (ref "D2A") (pin "2") (pinfunction "K_2") (pintype "passive"))
      (node (ref "D3A") (pin "2") (pinfunction "K_2") (pintype "passive"))
      (node (ref "D4A") (pin "2") (pinfunction "K_2") (pintype "passive"))
      (node (ref "D5A") (pin "2") (pinfunction "K_2") (pintype "passive"))
      (node (ref "RCOLA") (pin "2") (pinfunction "2_2") (pintype "passive"))
    )
    (net (code "12") (name "/ROW0") (class "Default")
      (node (ref "SW00") (pin "1") (pinfunction "1_1") (pintype "passive"))
      (node (ref "SW01") (pin "1") (pinfunction "1_1") (pintype "passive"))
      (node (ref "SW02") (pin "1") (pinfunction "1_1") (pintype "passive"))
      (node (ref "SW03") (pin "1") (pinfunction "1_1") (pintype "passive"))
      (node (ref "SW07") (pin "1") (pinfunction "1_1") (pintype "passive"))
      (node (ref "SW08") (pin "1") (pinfunction "1_1") (pintype "passive"))
      (node (ref "SW09") (pin "1") (pinfunction "1_1") (pintype "passive"))
      (node (ref "SW0A") (pin "1") (pinfunction "1_1") (pintype "passive"))
    )
    (net (code "13") (name "/ROW1") (class "Default")
      (node (ref "SW10") (pin "1") (pinfunction "1_1") (pintype "passive"))
      (node (ref "SW11") (pin "1") (pinfunction "1_1") (pintype "passive"))
      (node (ref "SW12") (pin "1") (pinfunction "1_1") (pintype "passive"))
      (node (ref "SW13") (pin "1") (pinfunction "1_1") (pintype "passive"))
      (node (ref "SW14") (pin "1") (pinfunction "1_1") (pintype "passive"))
      (node (ref "SW15") (pin "1") (pinfunction "1_1") (pintype "passive"))
      (node (ref "SW16") (pin "1") (pinfunction "1_1") (pintype "passive"))
      (node (ref "SW17") (pin "1") (pinfunction "1_1") (pintype "passive"))
      (node (ref "SW18") (pin "1") (pinfunction "1_1") (pintype "passive"))
      (node (ref "SW19") (pin "1") (pinfunction "1_1") (pintype "passive"))
      (node (ref "SW1A") (pin "1") (pinfunction "1_1") (pintype "passive"))
    )
    (net (code "14") (name "/ROW2") (class "Default")
      (node (ref "SW20") (pin "1") (pinfunction "1_1") (pintype "passive"))
      (node (ref "SW21") (pin "1") (pinfunction "1_1") (pintype "passive"))
      (node (ref "SW22") (pin "1") (pinfunction "1_1") (pintype "passive"))
      (node (ref "SW23") (pin "1") (pinfunction "1_1") (pintype "passive"))
      (node (ref "SW24") (pin "1") (pinfunction "1_1") (pintype "passive"))
      (node (ref "SW25") (pin "1") (pinfunction "1_1") (pintype "passive"))
      (node (ref "SW26") (pin "1") (pinfunction "1_1") (pintype "passive"))
      (node (ref "SW27") (pin "1") (pinfunction "1_1") (pintype "passive"))
      (node (ref "SW28") (pin "1") (pinfunction "1_1") (pintype "passive"))
      (node (ref "SW29") (pin "1") (pinfunction "1_1") (pintype "passive"))
      (node (ref "SW2A") (pin "1") (pinfunction "1_1") (pintype "passive"))
    )
    (net (code "15") (name "/ROW3") (class "Default")
      (node (ref "SW30") (pin "1") (pinfunction "1_1") (pintype "passive"))
      (node (ref "SW31") (pin "1") (pinfunction "1_1") (pintype "passive"))
      (node (ref "SW32") (pin "1") (pinfunction "1_1") (pintype "passive"))
      (node (ref "SW33") (pin "1") (pinfunction "1_1") (pintype "passive"))
      (node (ref "SW34") (pin "1") (pinfunction "1_1") (pintype "passive"))
      (node (ref "SW35") (pin "1") (pinfunction "1_1") (pintype "passive"))
      (node (ref "SW36") (pin "1") (pinfunction "1_1") (pintype "passive"))
      (node (ref "SW37") (pin "1") (pinfunction "1_1") (pintype "passive"))
      (node (ref "SW38") (pin "1") (pinfunction "1_1") (pintype "passive"))
      (node (ref "SW39") (pin "1") (pinfunction "1_1") (pintype "passive"))
      (node (ref "SW3A") (pin "1") (pinfunction "1_1") (pintype "passive"))
    )
    (net (code "16") (name "/ROW4") (class "Default")
      (node (ref "SW40") (pin "1") (pinfunction "1_1") (pintype "passive"))
      (node (ref "SW41") (pin "1") (pinfunction "1_1") (pintype "passive"))
      (node (ref "SW42") (pin "1") (pinfunction "1_1") (pintype "passive"))
      (node (ref "SW43") (pin "1") (pinfunction "1_1") (pintype "passive"))
      (node (ref "SW44") (pin "1") (pinfunction "1_1") (pintype "passive"))
      (node (ref "SW45") (pin "1") (pinfunction "1_1") (pintype "passive"))
      (node (ref "SW46") (pin "1") (pinfunction "1_1") (pintype "passive"))
      (node (ref "SW47") (pin "1") (pinfunction "1_1") (pintype "passive"))
      (node (ref "SW48") (pin "1") (pinfunction "1_1") (pintype "passive"))
      (node (ref "SW49") (pin "1") (pinfunction "1_1") (pintype "passive"))
      (node (ref "SW4A") (pin "1") (pinfunction "1_1") (pintype "passive"))
    )
    (net (code "17") (name "/ROW5") (class "Default")
      (node (ref "SW50") (pin "1") (pinfunction "1_1") (pintype "passive"))
      (node (ref "SW51") (pin "1") (pinfunction "1_1") (pintype "passive"))
      (node (ref "SW52") (pin "1") (pinfunction "1_1") (pintype "passive"))
      (node (ref "SW53") (pin "1") (pinfunction "1_1") (pintype "passive"))
      (node (ref "SW54") (pin "1") (pinfunction "1_1") (pintype "passive"))
      (node (ref "SW55") (pin "1") (pinfunction "1_1") (pintype "passive"))
      (node (ref "SW56") (pin "1") (pinfunction "1_1") (pintype "passive"))
      (node (ref "SW57") (pin "1") (pinfunction "1_1") (pintype "passive"))
      (node (ref "SW58") (pin "1") (pinfunction "1_1") (pintype "passive"))
      (node (ref "SW59") (pin "1") (pinfunction "1_1") (pintype "passive"))
      (node (ref "SW5A") (pin "1") (pinfunction "1_1") (pintype "passive"))
    )
    (net (code "18") (name "GND") (class "Default")
      (node (ref "RCOL0") (pin "1") (pinfunction "1_1") (pintype "passive"))
      (node (ref "RCOL1") (pin "1") (pinfunction "1_1") (pintype "passive"))
      (node (ref "RCOL2") (pin "1") (pinfunction "1_1") (pintype "passive"))
      (node (ref "RCOL3") (pin "1") (pinfunction "1_1") (pintype "passive"))
      (node (ref "RCOL4") (pin "1") (pinfunction "1_1") (pintype "passive"))
      (node (ref "RCOL5") (pin "1") (pinfunction "1_1") (pintype "passive"))
      (node (ref "RCOL6") (pin "1") (pinfunction "1_1") (pintype "passive"))
      (node (ref "RCOL7") (pin "1") (pinfunction "1_1") (pintype "passive"))
      (node (ref "RCOL8") (pin "1") (pinfunction "1_1") (pintype "passive"))
      (node (ref "RCOL9") (pin "1") (pinfunction "1_1") (pintype "passive"))
      (node (ref "RCOLA") (pin "1") (pinfunction "1_1") (pintype "passive"))
    )
    (net (code "19") (name "Net-(D00-A)") (class "Default")
      (node (ref "D00") (pin "1") (pinfunction "A_1") (pintype "passive"))
      (node (ref "SW00") (pin "2") (pinfunction "2_2") (pintype "passive"))
    )
    (net (code "20") (name "Net-(D0A-A)") (class "Default")
      (node (ref "D0A") (pin "1") (pinfunction "A_1") (pintype "passive"))
      (node (ref "SW0A") (pin "2") (pinfunction "2_2") (pintype "passive"))
    )
    (net (code "21") (name "Net-(D01-A)") (class "Default")
      (node (ref "D01") (pin "1") (pinfunction "A_1") (pintype "passive"))
      (node (ref "SW01") (pin "2") (pinfunction "2_2") (pintype "passive"))
    )
    (net (code "22") (name "Net-(D1A-A)") (class "Default")
      (node (ref "D1A") (pin "1") (pinfunction "A_1") (pintype "passive"))
      (node (ref "SW1A") (pin "2") (pinfunction "2_2") (pintype "passive"))
    )
    (net (code "23") (name "Net-(D02-A)") (class "Default")
      (node (ref "D02") (pin "1") (pinfunction "A_1") (pintype "passive"))
      (node (ref "SW02") (pin "2") (pinfunction "2_2") (pintype "passive"))
    )
    (net (code "24") (name "Net-(D2A-A)") (class "Default")
      (node (ref "D2A") (pin "1") (pinfunction "A_1") (pintype "passive"))
      (node (ref "SW2A") (pin "2") (pinfunction "2_2") (pintype "passive"))
    )
    (net (code "25") (name "Net-(D03-A)") (class "Default")
      (node (ref "D03") (pin "1") (pinfunction "A_1") (pintype "passive"))
      (node (ref "SW03") (pin "2") (pinfunction "2_2") (pintype "passive"))
    )
    (net (code "26") (name "Net-(D3A-A)") (class "Default")
      (node (ref "D3A") (pin "1") (pinfunction "A_1") (pintype "passive"))
      (node (ref "SW3A") (pin "2") (pinfunction "2_2") (pintype "passive"))
    )
    (net (code "27") (name "Net-(D4A-A)") (class "Default")
      (node (ref "D4A") (pin "1") (pinfunction "A_1") (pintype "passive"))
      (node (ref "SW4A") (pin "2") (pinfunction "2_2") (pintype "passive"))
    )
    (net (code "28") (name "Net-(D5A-A)") (class "Default")
      (node (ref "D5A") (pin "1") (pinfunction "A_1") (pintype "passive"))
      (node (ref "SW5A") (pin "2") (pinfunction "2_2") (pintype "passive"))
    )
    (net (code "29") (name "Net-(D07-A)") (class "Default")
      (node (ref "D07") (pin "1") (pinfunction "A_1") (pintype "passive"))
      (node (ref "SW07") (pin "2") (pinfunction "2_2") (pintype "passive"))
    )
    (net (code "30") (name "Net-(D08-A)") (class "Default")
      (node (ref "D08") (pin "1") (pinfunction "A_1") (pintype "passive"))
      (node (ref "SW08") (pin "2") (pinfunction "2_2") (pintype "passive"))
    )
    (net (code "31") (name "Net-(D09-A)") (class "Default")
      (node (ref "D09") (pin "1") (pinfunction "A_1") (pintype "passive"))
      (node (ref "SW09") (pin "2") (pinfunction "2_2") (pintype "passive"))
    )
    (net (code "32") (name "Net-(D10-A)") (class "Default")
      (node (ref "D10") (pin "1") (pinfunction "A_1") (pintype "passive"))
      (node (ref "SW10") (pin "2") (pinfunction "2_2") (pintype "passive"))
    )
    (net (code "33") (name "Net-(D11-A)") (class "Default")
      (node (ref "D11") (pin "1") (pinfunction "A_1") (pintype "passive"))
      (node (ref "SW11") (pin "2") (pinfunction "2_2") (pintype "passive"))
    )
    (net (code "34") (name "Net-(D12-A)") (class "Default")
      (node (ref "D12") (pin "1") (pinfunction "A_1") (pintype "passive"))
      (node (ref "SW12") (pin "2") (pinfunction "2_2") (pintype "passive"))
    )
    (net (code "35") (name "Net-(D13-A)") (class "Default")
      (node (ref "D13") (pin "1") (pinfunction "A_1") (pintype "passive"))
      (node (ref "SW13") (pin "2") (pinfunction "2_2") (pintype "passive"))
    )
    (net (code "36") (name "Net-(D14-A)") (class "Default")
      (node (ref "D14") (pin "1") (pinfunction "A_1") (pintype "passive"))
      (node (ref "SW14") (pin "2") (pinfunction "2_2") (pintype "passive"))
    )
    (net (code "37") (name "Net-(D15-A)") (class "Default")
      (node (ref "D15") (pin "1") (pinfunction "A_1") (pintype "passive"))
      (node (ref "SW15") (pin "2") (pinfunction "2_2") (pintype "passive"))
    )
    (net (code "38") (name "Net-(D16-A)") (class "Default")
      (node (ref "D16") (pin "1") (pinfunction "A_1") (pintype "passive"))
      (node (ref "SW16") (pin "2") (pinfunction "2_2") (pintype "passive"))
    )
    (net (code "39") (name "Net-(D17-A)") (class "Default")
      (node (ref "D17") (pin "1") (pinfunction "A_1") (pintype "passive"))
      (node (ref "SW17") (pin "2") (pinfunction "2_2") (pintype "passive"))
    )
    (net (code "40") (name "Net-(D18-A)") (class "Default")
      (node (ref "D18") (pin "1") (pinfunction "A_1") (pintype "passive"))
      (node (ref "SW18") (pin "2") (pinfunction "2_2") (pintype "passive"))
    )
    (net (code "41") (name "Net-(D19-A)") (class "Default")
      (node (ref "D19") (pin "1") (pinfunction "A_1") (pintype "passive"))
      (node (ref "SW19") (pin "2") (pinfunction "2_2") (pintype "passive"))
    )
    (net (code "42") (name "Net-(D20-A)") (class "Default")
      (node (ref "D20") (pin "1") (pinfunction "A_1") (pintype "passive"))
      (node (ref "SW20") (pin "2") (pinfunction "2_2") (pintype "passive"))
    )
    (net (code "43") (name "Net-(D21-A)") (class "Default")
      (node (ref "D21") (pin "1") (pinfunction "A_1") (pintype "passive"))
      (node (ref "SW21") (pin "2") (pinfunction "2_2") (pintype "passive"))
    )
    (net (code "44") (name "Net-(D22-A)") (class "Default")
      (node (ref "D22") (pin "1") (pinfunction "A_1") (pintype "passive"))
      (node (ref "SW22") (pin "2") (pinfunction "2_2") (pintype "passive"))
    )
    (net (code "45") (name "Net-(D23-A)") (class "Default")
      (node (ref "D23") (pin "1") (pinfunction "A_1") (pintype "passive"))
      (node (ref "SW23") (pin "2") (pinfunction "2_2") (pintype "passive"))
    )
    (net (code "46") (name "Net-(D24-A)") (class "Default")
      (node (ref "D24") (pin "1") (pinfunction "A_1") (pintype "passive"))
      (node (ref "SW24") (pin "2") (pinfunction "2_2") (pintype "passive"))
    )
    (net (code "47") (name "Net-(D25-A)") (class "Default")
      (node (ref "D25") (pin "1") (pinfunction "A_1") (pintype "passive"))
      (node (ref "SW25") (pin "2") (pinfunction "2_2") (pintype "passive"))
    )
    (net (code "48") (name "Net-(D26-A)") (class "Default")
      (node (ref "D26") (pin "1") (pinfunction "A_1") (pintype "passive"))
      (node (ref "SW26") (pin "2") (pinfunction "2_2") (pintype "passive"))
    )
    (net (code "49") (name "Net-(D27-A)") (class "Default")
      (node (ref "D27") (pin "1") (pinfunction "A_1") (pintype "passive"))
      (node (ref "SW27") (pin "2") (pinfunction "2_2") (pintype "passive"))
    )
    (net (code "50") (name "Net-(D28-A)") (class "Default")
      (node (ref "D28") (pin "1") (pinfunction "A_1") (pintype "passive"))
      (node (ref "SW28") (pin "2") (pinfunction "2_2") (pintype "passive"))
    )
    (net (code "51") (name "Net-(D29-A)") (class "Default")
      (node (ref "D29") (pin "1") (pinfunction "A_1") (pintype "passive"))
      (node (ref "SW29") (pin "2") (pinfunction "2_2") (pintype "passive"))
    )
    (net (code "52") (name "Net-(D30-A)") (class "Default")
      (node (ref "D30") (pin "1") (pinfunction "A_1") (pintype "passive"))
      (node (ref "SW30") (pin "2") (pinfunction "2_2") (pintype "passive"))
    )
    (net (code "53") (name "Net-(D31-A)") (class "Default")
      (node (ref "D31") (pin "1") (pinfunction "A_1") (pintype "passive"))
      (node (ref "SW31") (pin "2") (pinfunction "2_2") (pintype "passive"))
    )
    (net (code "54") (name "Net-(D32-A)") (class "Default")
      (node (ref "D32") (pin "1") (pinfunction "A_1") (pintype "passive"))
      (node (ref "SW32") (pin "2") (pinfunction "2_2") (pintype "passive"))
    )
    (net (code "55") (name "Net-(D33-A)") (class "Default")
      (node (ref "D33") (pin "1") (pinfunction "A_1") (pintype "passive"))
      (node (ref "SW33") (pin "2") (pinfunction "2_2") (pintype "passive"))
    )
    (net (code "56") (name "Net-(D34-A)") (class "Default")
      (node (ref "D34") (pin "1") (pinfunction "A_1") (pintype "passive"))
      (node (ref "SW34") (pin "2") (pinfunction "2_2") (pintype "passive"))
    )
    (net (code "57") (name "Net-(D35-A)") (class "Default")
      (node (ref "D35") (pin "1") (pinfunction "A_1") (pintype "passive"))
      (node (ref "SW35") (pin "2") (pinfunction "2_2") (pintype "passive"))
    )
    (net (code "58") (name "Net-(D36-A)") (class "Default")
      (node (ref "D36") (pin "1") (pinfunction "A_1") (pintype "passive"))
      (node (ref "SW36") (pin "2") (pinfunction "2_2") (pintype "passive"))
    )
    (net (code "59") (name "Net-(D37-A)") (class "Default")
      (node (ref "D37") (pin "1") (pinfunction "A_1") (pintype "passive"))
      (node (ref "SW37") (pin "2") (pinfunction "2_2") (pintype "passive"))
    )
    (net (code "60") (name "Net-(D38-A)") (class "Default")
      (node (ref "D38") (pin "1") (pinfunction "A_1") (pintype "passive"))
      (node (ref "SW38") (pin "2") (pinfunction "2_2") (pintype "passive"))
    )
    (net (code "61") (name "Net-(D39-A)") (class "Default")
      (node (ref "D39") (pin "1") (pinfunction "A_1") (pintype "passive"))
      (node (ref "SW39") (pin "2") (pinfunction "2_2") (pintype "passive"))
    )
    (net (code "62") (name "Net-(D40-A)") (class "Default")
      (node (ref "D40") (pin "1") (pinfunction "A_1") (pintype "passive"))
      (node (ref "SW40") (pin "2") (pinfunction "2_2") (pintype "passive"))
    )
    (net (code "63") (name "Net-(D41-A)") (class "Default")
      (node (ref "D41") (pin "1") (pinfunction "A_1") (pintype "passive"))
      (node (ref "SW41") (pin "2") (pinfunction "2_2") (pintype "passive"))
    )
    (net (code "64") (name "Net-(D42-A)") (class "Default")
      (node (ref "D42") (pin "1") (pinfunction "A_1") (pintype "passive"))
      (node (ref "SW42") (pin "2") (pinfunction "2_2") (pintype "passive"))
    )
    (net (code "65") (name "Net-(D43-A)") (class "Default")
      (node (ref "D43") (pin "1") (pinfunction "A_1") (pintype "passive"))
      (node (ref "SW43") (pin "2") (pinfunction "2_2") (pintype "passive"))
    )
    (net (code "66") (name "Net-(D44-A)") (class "Default")
      (node (ref "D44") (pin "1") (pinfunction "A_1") (pintype "passive"))
      (node (ref "SW44") (pin "2") (pinfunction "2_2") (pintype "passive"))
    )
    (net (code "67") (name "Net-(D45-A)") (class "Default")
      (node (ref "D45") (pin "1") (pinfunction "A_1") (pintype "passive"))
      (node (ref "SW45") (pin "2") (pinfunction "2_2") (pintype "passive"))
    )
    (net (code "68") (name "Net-(D46-A)") (class "Default")
      (node (ref "D46") (pin "1") (pinfunction "A_1") (pintype "passive"))
      (node (ref "SW46") (pin "2") (pinfunction "2_2") (pintype "passive"))
    )
    (net (code "69") (name "Net-(D47-A)") (class "Default")
      (node (ref "D47") (pin "1") (pinfunction "A_1") (pintype "passive"))
      (node (ref "SW47") (pin "2") (pinfunction "2_2") (pintype "passive"))
    )
    (net (code "70") (name "Net-(D48-A)") (class "Default")
      (node (ref "D48") (pin "1") (pinfunction "A_1") (pintype "passive"))
      (node (ref "SW48") (pin "2") (pinfunction "2_2") (pintype "passive"))
    )
    (net (code "71") (name "Net-(D49-A)") (class "Default")
      (node (ref "D49") (pin "1") (pinfunction "A_1") (pintype "passive"))
      (node (ref "SW49") (pin "2") (pinfunction "2_2") (pintype "passive"))
    )
    (net (code "72") (name "Net-(D50-A)") (class "Default")
      (node (ref "D50") (pin "1") (pinfunction "A_1") (pintype "passive"))
      (node (ref "SW50") (pin "2") (pinfunction "2_2") (pintype "passive"))
    )
    (net (code "73") (name "Net-(D51-A)") (class "Default")
      (node (ref "D51") (pin "1") (pinfunction "A_1") (pintype "passive"))
      (node (ref "SW51") (pin "2") (pinfunction "2_2") (pintype "passive"))
    )
    (net (code "74") (name "Net-(D52-A)") (class "Default")
      (node (ref "D52") (pin "1") (pinfunction "A_1") (pintype "passive"))
      (node (ref "SW52") (pin "2") (pinfunction "2_2") (pintype "passive"))
    )
    (net (code "75") (name "Net-(D53-A)") (class "Default")
      (node (ref "D53") (pin "1") (pinfunction "A_1") (pintype "passive"))
      (node (ref "SW53") (pin "2") (pinfunction "2_2") (pintype "passive"))
    )
    (net (code "76") (name "Net-(D54-A)") (class "Default")
      (node (ref "D54") (pin "1") (pinfunction "A_1") (pintype "passive"))
      (node (ref "SW54") (pin "2") (pinfunction "2_2") (pintype "passive"))
    )
    (net (code "77") (name "Net-(D55-A)") (class "Default")
      (node (ref "D55") (pin "1") (pinfunction "A_1") (pintype "passive"))
      (node (ref "SW55") (pin "2") (pinfunction "2_2") (pintype "passive"))
    )
    (net (code "78") (name "Net-(D56-A)") (class "Default")
      (node (ref "D56") (pin "1") (pinfunction "A_1") (pintype "passive"))
      (node (ref "SW56") (pin "2") (pinfunction "2_2") (pintype "passive"))
    )
    (net (code "79") (name "Net-(D57-A)") (class "Default")
      (node (ref "D57") (pin "1") (pinfunction "A_1") (pintype "passive"))
      (node (ref "SW57") (pin "2") (pinfunction "2_2") (pintype "passive"))
    )
    (net (code "80") (name "Net-(D58-A)") (class "Default")
      (node (ref "D58") (pin "1") (pinfunction "A_1") (pintype "passive"))
      (node (ref "SW58") (pin "2") (pinfunction "2_2") (pintype "passive"))
    )
    (net (code "81") (name "Net-(D59-A)") (class "Default")
      (node (ref "D59") (pin "1") (pinfunction "A_1") (pintype "passive"))
      (node (ref "SW59") (pin "2") (pinfunction "2_2") (pintype "passive"))
    )
  )
)
